# OpenPack_BATMOD_V2p0_CHRG.net
KiCad netlist of a schematic drawn in Altium Designer
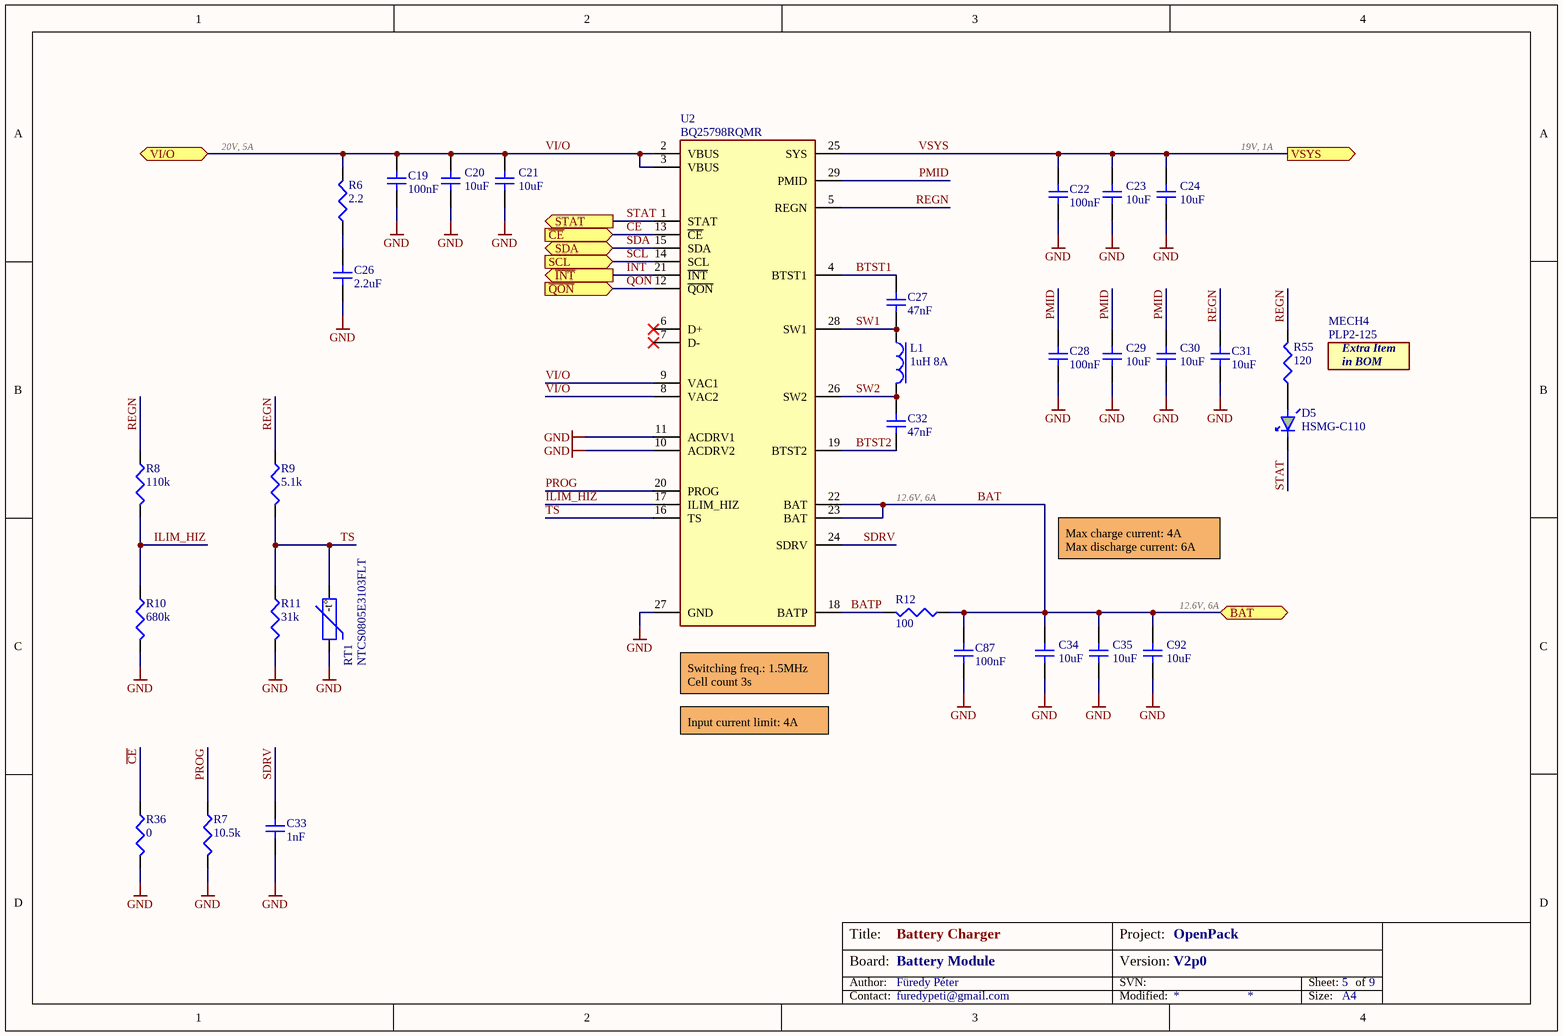
[diagram p0: OpenPack_BATMOD_V2p0_CHRG.SchDoc]

(export (version "E")
  (design (tool "Eeschema 10.0.6"))
  (components
    (comp (ref "C19")
      (value "100nF")
      (footprint "CAP_0603")
      (description "MLCC capacitor")
      (libsource (lib "SCHLIB") (part "NP-CAPACITOR"))
    )
    (comp (ref "C20")
      (value "10uF")
      (footprint "CAP_1210")
      (description "UMK325BJ106KM-P")
      (fields (field (name "PART NUMBER") "810-CGA6P1X7R1N106K2"))
      (libsource (lib "SCHLIB") (part "NP-CAPACITOR"))
    )
    (comp (ref "C21")
      (value "10uF")
      (footprint "CAP_1210")
      (description "UMK325BJ106KM-P")
      (fields (field (name "PART NUMBER") "810-CGA6P1X7R1N106K2"))
      (libsource (lib "SCHLIB") (part "NP-CAPACITOR"))
    )
    (comp (ref "C22")
      (value "100nF")
      (footprint "CAP_0603")
      (description "MLCC capacitor")
      (libsource (lib "SCHLIB") (part "NP-CAPACITOR"))
    )
    (comp (ref "C23")
      (value "10uF")
      (footprint "CAP_1210")
      (description "UMK325BJ106KM-P")
      (fields (field (name "PART NUMBER") "810-CGA6P1X7R1N106K2"))
      (libsource (lib "SCHLIB") (part "NP-CAPACITOR"))
    )
    (comp (ref "C24")
      (value "10uF")
      (footprint "CAP_1210")
      (description "UMK325BJ106KM-P")
      (fields (field (name "PART NUMBER") "810-CGA6P1X7R1N106K2"))
      (libsource (lib "SCHLIB") (part "NP-CAPACITOR"))
    )
    (comp (ref "C26")
      (value "2.2uF")
      (footprint "CAP-0805")
      (description "MLCC capacitor")
      (libsource (lib "SCHLIB") (part "NP-CAPACITOR"))
    )
    (comp (ref "C27")
      (value "47nF")
      (footprint "CAP_0603")
      (description "MLCC capacitor")
      (libsource (lib "SCHLIB") (part "NP-CAPACITOR"))
    )
    (comp (ref "C28")
      (value "100nF")
      (footprint "CAP_0603")
      (description "MLCC capacitor")
      (libsource (lib "SCHLIB") (part "NP-CAPACITOR"))
    )
    (comp (ref "C29")
      (value "10uF")
      (footprint "CAP_1210")
      (description "UMK325BJ106KM-P")
      (fields (field (name "PART NUMBER") "810-CGA6P1X7R1N106K2"))
      (libsource (lib "SCHLIB") (part "NP-CAPACITOR"))
    )
    (comp (ref "C30")
      (value "10uF")
      (footprint "CAP_1210")
      (description "UMK325BJ106KM-P")
      (fields (field (name "PART NUMBER") "810-CGA6P1X7R1N106K2"))
      (libsource (lib "SCHLIB") (part "NP-CAPACITOR"))
    )
    (comp (ref "C31")
      (value "10uF")
      (footprint "CAP_0603")
      (description "MLCC capacitor")
      (libsource (lib "SCHLIB") (part "NP-CAPACITOR"))
    )
    (comp (ref "C32")
      (value "47nF")
      (footprint "CAP_0603")
      (description "MLCC capacitor")
      (libsource (lib "SCHLIB") (part "NP-CAPACITOR"))
    )
    (comp (ref "C33")
      (value "1nF")
      (footprint "CAP_0603")
      (description "MLCC capacitor")
      (libsource (lib "SCHLIB") (part "NP-CAPACITOR"))
    )
    (comp (ref "C34")
      (value "10uF")
      (footprint "CAP_1210")
      (description "UMK325BJ106KM-P")
      (fields (field (name "PART NUMBER") "810-CGA6P1X7R1N106K2"))
      (libsource (lib "SCHLIB") (part "NP-CAPACITOR"))
    )
    (comp (ref "C35")
      (value "10uF")
      (footprint "CAP_1210")
      (description "UMK325BJ106KM-P")
      (fields (field (name "PART NUMBER") "810-CGA6P1X7R1N106K2"))
      (libsource (lib "SCHLIB") (part "NP-CAPACITOR"))
    )
    (comp (ref "C87")
      (value "100nF")
      (footprint "CAP_0603")
      (description "MLCC capacitor")
      (libsource (lib "SCHLIB") (part "NP-CAPACITOR"))
    )
    (comp (ref "C92")
      (value "10uF")
      (footprint "CAP_1210")
      (description "UMK325BJ106KM-P")
      (fields (field (name "PART NUMBER") "810-CGA6P1X7R1N106K2"))
      (libsource (lib "SCHLIB") (part "NP-CAPACITOR"))
    )
    (comp (ref "D5")
      (value "HSMG-C110")
      (footprint "LED_SMD_90DEG_GRE")
      (description "Green LED, 90deg")
      (fields (field (name "PART NUMBER") "630-HSMG-C110"))
      (libsource (lib "SCHLIB") (part "HSMG-C110"))
    )
    (comp (ref "L1")
      (value "1uH 8A")
      (footprint "WE-LHMI_7030")
      (description "Ferrit core coil, 1uH 8A, 10mR")
      (fields (field (name "PART NUMBER") "710-74437346010"))
      (libsource (lib "SCHLIB") (part "Inductance - 1uH"))
    )
    (comp (ref "MECH4")
      (value "PLP2-125")
      (description "LED Light Pipe, 3mm round lense")
      (fields (field (name "PART NUMBER") "749-PLP2-125"))
      (libsource (lib "SCHLIB") (part "PLP2-125"))
    )
    (comp (ref "R6")
      (value "2.2")
      (footprint "RES-0805")
      (description "Metal Film Resistor")
      (libsource (lib "SCHLIB") (part "RESISTOR"))
    )
    (comp (ref "R7")
      (value "10.5k")
      (footprint "RES-0603")
      (description "Metal Film Resistor")
      (libsource (lib "SCHLIB") (part "RESISTOR"))
    )
    (comp (ref "R8")
      (value "110k")
      (footprint "RES-0603")
      (description "Metal Film Resistor")
      (libsource (lib "SCHLIB") (part "RESISTOR"))
    )
    (comp (ref "R9")
      (value "5.1k")
      (footprint "RES-0603")
      (description "Metal Film Resistor")
      (libsource (lib "SCHLIB") (part "RESISTOR"))
    )
    (comp (ref "R10")
      (value "680k")
      (footprint "RES-0603")
      (description "Metal Film Resistor")
      (libsource (lib "SCHLIB") (part "RESISTOR"))
    )
    (comp (ref "R11")
      (value "31k")
      (footprint "RES-0603")
      (description "Metal Film Resistor")
      (libsource (lib "SCHLIB") (part "RESISTOR"))
    )
    (comp (ref "R12")
      (value "100")
      (footprint "RES-0603")
      (description "Metal Film Resistor")
      (libsource (lib "SCHLIB") (part "RESISTOR"))
    )
    (comp (ref "R36")
      (value "0")
      (footprint "RES-0603")
      (description "Metal Film Resistor")
      (libsource (lib "SCHLIB") (part "RESISTOR"))
    )
    (comp (ref "R55")
      (value "120")
      (footprint "RES-0603")
      (description "Metal Film Resistor")
      (libsource (lib "SCHLIB") (part "RESISTOR"))
    )
    (comp (ref "RT1")
      (value "NTCS0805E3103FLT")
      (footprint "RES-0805")
      (description "NTC (Negative Temperature Coefficient) Thermistors 10Kohms 1%")
      (fields (field (name "PART NUMBER") "594-NTCS0805E3103FLT"))
      (libsource (lib "SCHLIB") (part "NTCS0805E3103FLT"))
    )
    (comp (ref "U2")
      (value "BQ25798RQMR")
      (footprint "QFN 29")
      (description "Battery Management I C controlled 1-4- cell 5-A buck-boost")
      (fields (field (name "PART NUMBER") "595-BQ25798RQMR"))
      (libsource (lib "SCHLIB") (part "BQ25798RQMR"))
    )
  )
  (nets
    (net (code "1") (name "/BAT") (class "Default")
      (node (ref "C34") (pin "2") (pinfunction "2_2") (pintype "passive"))
      (node (ref "C35") (pin "2") (pinfunction "2_2") (pintype "passive"))
      (node (ref "C87") (pin "2") (pinfunction "2_2") (pintype "passive"))
      (node (ref "C92") (pin "2") (pinfunction "2_2") (pintype "passive"))
      (node (ref "R12") (pin "1") (pintype "passive"))
      (node (ref "U2") (pin "22") (pinfunction "BAT_22") (pintype "passive"))
      (node (ref "U2") (pin "23") (pinfunction "BAT_23") (pintype "passive"))
    )
    (net (code "2") (name "/BATP") (class "Default")
      (node (ref "R12") (pin "2") (pintype "passive"))
      (node (ref "U2") (pin "18") (pinfunction "BATP_18") (pintype "passive"))
    )
    (net (code "3") (name "/BTST1") (class "Default")
      (node (ref "C27") (pin "2") (pinfunction "2_2") (pintype "passive"))
      (node (ref "U2") (pin "4") (pinfunction "BTST1_4") (pintype "passive"))
    )
    (net (code "4") (name "/BTST2") (class "Default")
      (node (ref "C32") (pin "1") (pinfunction "1_1") (pintype "passive"))
      (node (ref "U2") (pin "19") (pinfunction "BTST2_19") (pintype "passive"))
    )
    (net (code "5") (name "/ILIM_HIZ") (class "Default")
      (node (ref "R10") (pin "1") (pintype "passive"))
      (node (ref "R8") (pin "2") (pintype "passive"))
      (node (ref "U2") (pin "17") (pinfunction "ILIM_HIZ_17") (pintype "passive"))
    )
    (net (code "6") (name "/PMID") (class "Default")
      (node (ref "C28") (pin "2") (pinfunction "2_2") (pintype "passive"))
      (node (ref "C29") (pin "2") (pinfunction "2_2") (pintype "passive"))
      (node (ref "C30") (pin "2") (pinfunction "2_2") (pintype "passive"))
      (node (ref "U2") (pin "29") (pinfunction "PMID_29") (pintype "passive"))
    )
    (net (code "7") (name "/PROG") (class "Default")
      (node (ref "R7") (pin "1") (pintype "passive"))
      (node (ref "U2") (pin "20") (pinfunction "PROG_20") (pintype "passive"))
    )
    (net (code "8") (name "/REGN") (class "Default")
      (node (ref "C31") (pin "2") (pinfunction "2_2") (pintype "passive"))
      (node (ref "R55") (pin "1") (pintype "passive"))
      (node (ref "R8") (pin "1") (pintype "passive"))
      (node (ref "R9") (pin "1") (pintype "passive"))
      (node (ref "U2") (pin "5") (pinfunction "REGN_5") (pintype "passive"))
    )
    (net (code "9") (name "/SCL") (class "Default")
      (node (ref "U2") (pin "14") (pinfunction "SCL_14") (pintype "passive"))
    )
    (net (code "10") (name "/SDA") (class "Default")
      (node (ref "U2") (pin "15") (pinfunction "SDA_15") (pintype "passive"))
    )
    (net (code "11") (name "/SDRV") (class "Default")
      (node (ref "C33") (pin "2") (pinfunction "2_2") (pintype "passive"))
      (node (ref "U2") (pin "24") (pinfunction "SDRV_24") (pintype "passive"))
    )
    (net (code "12") (name "/STAT") (class "Default")
      (node (ref "D5") (pin "K") (pinfunction "2_K") (pintype "passive"))
      (node (ref "U2") (pin "1") (pinfunction "STAT_1") (pintype "passive"))
    )
    (net (code "13") (name "/SW1") (class "Default")
      (node (ref "C27") (pin "1") (pinfunction "1_1") (pintype "passive"))
      (node (ref "L1") (pin "1") (pinfunction "1_1") (pintype "passive"))
      (node (ref "U2") (pin "28") (pinfunction "SW1_28") (pintype "passive"))
    )
    (net (code "14") (name "/SW2") (class "Default")
      (node (ref "C32") (pin "2") (pinfunction "2_2") (pintype "passive"))
      (node (ref "L1") (pin "2") (pinfunction "2_2") (pintype "passive"))
      (node (ref "U2") (pin "26") (pinfunction "SW2_26") (pintype "passive"))
    )
    (net (code "15") (name "/TS") (class "Default")
      (node (ref "R11") (pin "1") (pintype "passive"))
      (node (ref "R9") (pin "2") (pintype "passive"))
      (node (ref "RT1") (pin "2") (pintype "passive"))
      (node (ref "U2") (pin "16") (pinfunction "TS_16") (pintype "passive"))
    )
    (net (code "16") (name "/VI{slash}O") (class "Default")
      (node (ref "C19") (pin "2") (pinfunction "2_2") (pintype "passive"))
      (node (ref "C20") (pin "2") (pinfunction "2_2") (pintype "passive"))
      (node (ref "C21") (pin "2") (pinfunction "2_2") (pintype "passive"))
      (node (ref "R6") (pin "2") (pintype "passive"))
      (node (ref "U2") (pin "2") (pinfunction "VBUS_2") (pintype "passive"))
      (node (ref "U2") (pin "3") (pinfunction "VBUS_3") (pintype "passive"))
      (node (ref "U2") (pin "8") (pinfunction "VAC2_8") (pintype "passive"))
      (node (ref "U2") (pin "9") (pinfunction "VAC1_9") (pintype "passive"))
    )
    (net (code "17") (name "/VSYS") (class "Default")
      (node (ref "C22") (pin "2") (pinfunction "2_2") (pintype "passive"))
      (node (ref "C23") (pin "2") (pinfunction "2_2") (pintype "passive"))
      (node (ref "C24") (pin "2") (pinfunction "2_2") (pintype "passive"))
      (node (ref "U2") (pin "25") (pinfunction "SYS_25") (pintype "passive"))
    )
    (net (code "18") (name "/~{CE}") (class "Default")
      (node (ref "R36") (pin "1") (pintype "passive"))
      (node (ref "U2") (pin "13") (pinfunction "~{CE}_13") (pintype "passive"))
    )
    (net (code "19") (name "/~{INT}") (class "Default")
      (node (ref "U2") (pin "21") (pinfunction "~{INT}_21") (pintype "passive"))
    )
    (net (code "20") (name "/~{QON}") (class "Default")
      (node (ref "U2") (pin "12") (pinfunction "~{QON}_12") (pintype "passive"))
    )
    (net (code "21") (name "GND") (class "Default")
      (node (ref "C19") (pin "1") (pinfunction "1_1") (pintype "passive"))
      (node (ref "C20") (pin "1") (pinfunction "1_1") (pintype "passive"))
      (node (ref "C21") (pin "1") (pinfunction "1_1") (pintype "passive"))
      (node (ref "C22") (pin "1") (pinfunction "1_1") (pintype "passive"))
      (node (ref "C23") (pin "1") (pinfunction "1_1") (pintype "passive"))
      (node (ref "C24") (pin "1") (pinfunction "1_1") (pintype "passive"))
      (node (ref "C26") (pin "1") (pinfunction "1_1") (pintype "passive"))
      (node (ref "C28") (pin "1") (pinfunction "1_1") (pintype "passive"))
      (node (ref "C29") (pin "1") (pinfunction "1_1") (pintype "passive"))
      (node (ref "C30") (pin "1") (pinfunction "1_1") (pintype "passive"))
      (node (ref "C31") (pin "1") (pinfunction "1_1") (pintype "passive"))
      (node (ref "C33") (pin "1") (pinfunction "1_1") (pintype "passive"))
      (node (ref "C34") (pin "1") (pinfunction "1_1") (pintype "passive"))
      (node (ref "C35") (pin "1") (pinfunction "1_1") (pintype "passive"))
      (node (ref "C87") (pin "1") (pinfunction "1_1") (pintype "passive"))
      (node (ref "C92") (pin "1") (pinfunction "1_1") (pintype "passive"))
      (node (ref "R10") (pin "2") (pintype "passive"))
      (node (ref "R11") (pin "2") (pintype "passive"))
      (node (ref "R36") (pin "2") (pintype "passive"))
      (node (ref "R7") (pin "2") (pintype "passive"))
      (node (ref "RT1") (pin "1") (pintype "passive"))
      (node (ref "U2") (pin "10") (pinfunction "ACDRV2_10") (pintype "passive"))
      (node (ref "U2") (pin "11") (pinfunction "ACDRV1_11") (pintype "passive"))
      (node (ref "U2") (pin "27") (pinfunction "GND_27") (pintype "passive"))
    )
    (net (code "22") (name "Net-(C26-Pad2)") (class "Default")
      (node (ref "C26") (pin "2") (pinfunction "2_2") (pintype "passive"))
      (node (ref "R6") (pin "1") (pintype "passive"))
    )
    (net (code "23") (name "Net-(D5-1)") (class "Default")
      (node (ref "D5") (pin "A") (pinfunction "1_A") (pintype "passive"))
      (node (ref "R55") (pin "2") (pintype "passive"))
    )
    (net (code "24") (name "unconnected-(U2-D+-Pad6)") (class "Default")
      (node (ref "U2") (pin "6") (pinfunction "D+_6") (pintype "passive+no_connect"))
    )
    (net (code "25") (name "unconnected-(U2-D--Pad7)") (class "Default")
      (node (ref "U2") (pin "7") (pinfunction "D-_7") (pintype "passive+no_connect"))
    )
  )
)
